# Pi_OS_v1.net
KiCad netlist of a schematic drawn in EAGLE
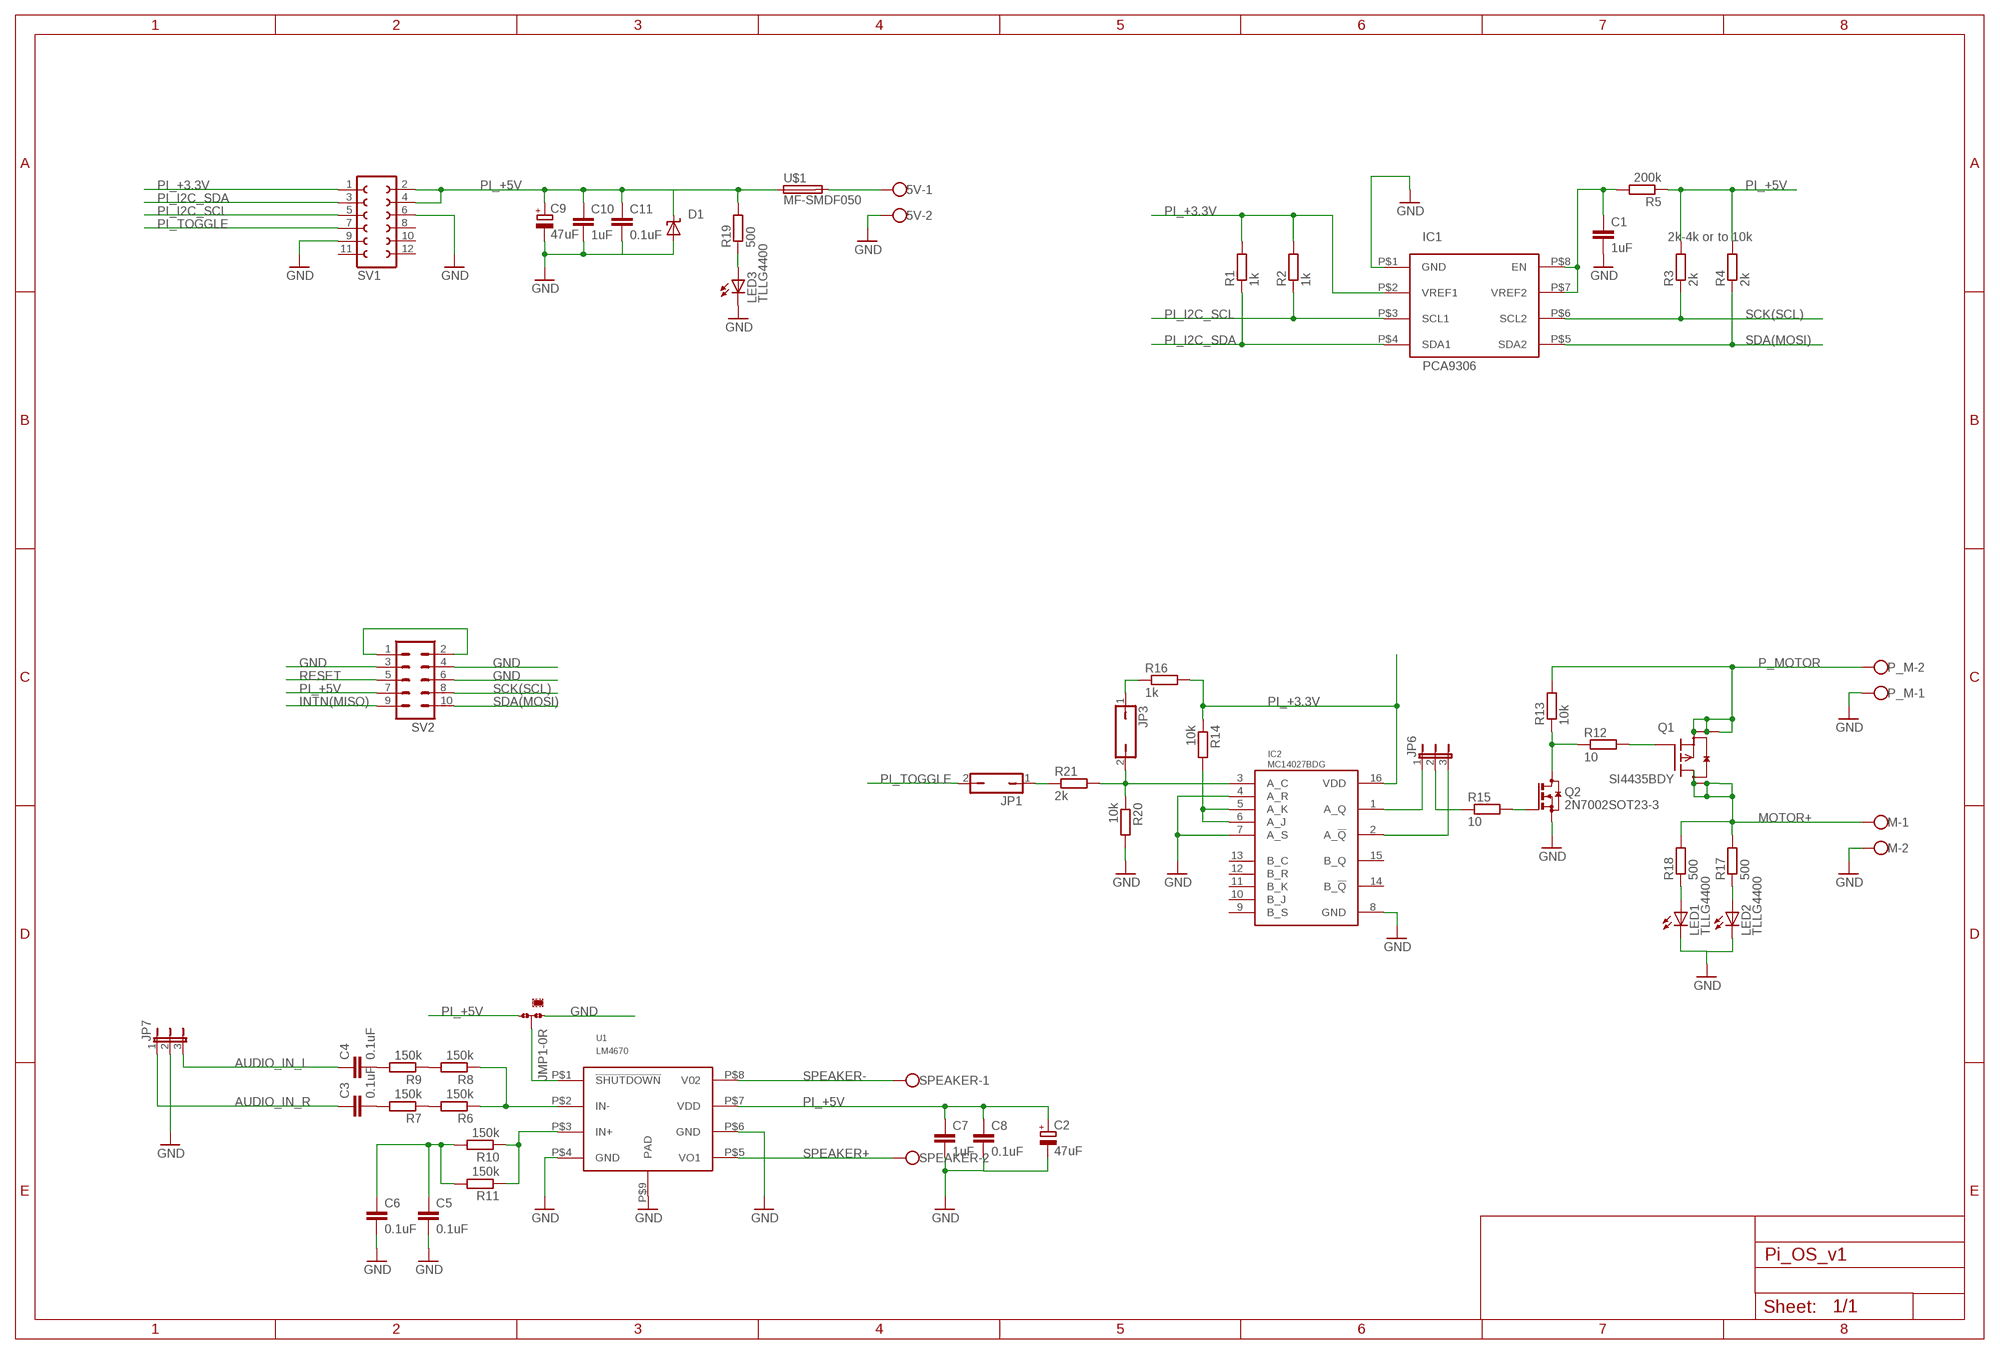
[diagram p0: schematic, sheet 1]

(export (version "E")
  (design (tool "Eeschema 10.0.6"))
  (components
    (comp (ref "5V")
      (value "W237-102")
      (footprint "eagle-import:W237-102")
      (fields (field (name "MPN") "237-102"))
      (libsource (lib "eagle-import") (part "W237-102"))
    )
    (comp (ref "C1")
      (value "1uF")
      (footprint "eagle-import:C1206")
      (libsource (lib "eagle-import") (part "C-EUC1206"))
    )
    (comp (ref "C2")
      (value "47uF")
      (footprint "eagle-import:153CLV-0505")
      (libsource (lib "eagle-import") (part "CPOL-EU153CLV-0505"))
    )
    (comp (ref "C3")
      (value "0.1uF")
      (footprint "eagle-import:C1206")
      (libsource (lib "eagle-import") (part "C-EUC1206"))
    )
    (comp (ref "C4")
      (value "0.1uF")
      (footprint "eagle-import:C1206")
      (libsource (lib "eagle-import") (part "C-EUC1206"))
    )
    (comp (ref "C5")
      (value "0.1uF")
      (footprint "eagle-import:C1206")
      (libsource (lib "eagle-import") (part "C-EUC1206"))
    )
    (comp (ref "C6")
      (value "0.1uF")
      (footprint "eagle-import:C1206")
      (libsource (lib "eagle-import") (part "C-EUC1206"))
    )
    (comp (ref "C7")
      (value "1uF")
      (footprint "eagle-import:C1206")
      (libsource (lib "eagle-import") (part "C-EUC1206"))
    )
    (comp (ref "C8")
      (value "0.1uF")
      (footprint "eagle-import:C1206")
      (libsource (lib "eagle-import") (part "C-EUC1206"))
    )
    (comp (ref "C9")
      (value "47uF")
      (footprint "eagle-import:153CLV-0505")
      (libsource (lib "eagle-import") (part "CPOL-EU153CLV-0505"))
    )
    (comp (ref "C10")
      (value "1uF")
      (footprint "eagle-import:C1206")
      (libsource (lib "eagle-import") (part "C-EUC1206"))
    )
    (comp (ref "C11")
      (value "0.1uF")
      (footprint "eagle-import:C1206")
      (libsource (lib "eagle-import") (part "C-EUC1206"))
    )
    (comp (ref "D1")
      (value "SUPPRESSOR-SMBJ")
      (footprint "eagle-import:SMBJ")
      (libsource (lib "eagle-import") (part "SUPPRESSOR-SMBJ"))
    )
    (comp (ref "IC1")
      (value "PCA9306")
      (footprint "eagle-import:TSSOP8")
      (libsource (lib "eagle-import") (part "PCA9306"))
    )
    (comp (ref "IC2")
      (value "MC14027BDG")
      (footprint "eagle-import:SOIC16")
      (libsource (lib "eagle-import") (part "MC14027BDG"))
    )
    (comp (ref "JMP1")
      (value "0R-JUMPB")
      (footprint "eagle-import:B0R-JMP")
      (libsource (lib "eagle-import") (part "0R-JUMPB"))
    )
    (comp (ref "JP1")
      (value "JP1Q")
      (footprint "eagle-import:JP1")
      (libsource (lib "eagle-import") (part "JP1Q"))
    )
    (comp (ref "JP3")
      (value "JP1Q")
      (footprint "eagle-import:JP1")
      (libsource (lib "eagle-import") (part "JP1Q"))
    )
    (comp (ref "JP6")
      (value "JP2E")
      (footprint "eagle-import:JP2")
      (libsource (lib "eagle-import") (part "JP2E"))
    )
    (comp (ref "JP7")
      (value "JP2E")
      (footprint "eagle-import:JP2")
      (libsource (lib "eagle-import") (part "JP2E"))
    )
    (comp (ref "LED1")
      (value "TLLG4400")
      (footprint "eagle-import:LED3MM")
      (fields (field (name "MF") "VISHAY SEMICONDUCTOR"))
      (libsource (lib "eagle-import") (part "TLLG4400"))
    )
    (comp (ref "LED2")
      (value "TLLG4400")
      (footprint "eagle-import:LED3MM")
      (fields (field (name "MF") "VISHAY SEMICONDUCTOR"))
      (libsource (lib "eagle-import") (part "TLLG4400"))
    )
    (comp (ref "LED3")
      (value "TLLG4400")
      (footprint "eagle-import:LED3MM")
      (fields (field (name "MF") "VISHAY SEMICONDUCTOR"))
      (libsource (lib "eagle-import") (part "TLLG4400"))
    )
    (comp (ref "M")
      (value "W237-102")
      (footprint "eagle-import:W237-102")
      (fields (field (name "MPN") "237-102"))
      (libsource (lib "eagle-import") (part "W237-102"))
    )
    (comp (ref "P_M")
      (value "W237-102")
      (footprint "eagle-import:W237-102")
      (fields (field (name "MPN") "237-102"))
      (libsource (lib "eagle-import") (part "W237-102"))
    )
    (comp (ref "Q1")
      (value "SI4435BDY")
      (footprint "eagle-import:SOIC8")
      (libsource (lib "eagle-import") (part "SI4435BDY"))
    )
    (comp (ref "Q2")
      (value "2N7002SOT23-3")
      (footprint "eagle-import:SOT23")
      (libsource (lib "eagle-import") (part "2N7002SOT23-3"))
    )
    (comp (ref "R1")
      (value "1k")
      (footprint "eagle-import:R0603")
      (libsource (lib "eagle-import") (part "R-EU_R0603"))
    )
    (comp (ref "R2")
      (value "1k")
      (footprint "eagle-import:R0603")
      (libsource (lib "eagle-import") (part "R-EU_R0603"))
    )
    (comp (ref "R3")
      (value "2k")
      (footprint "eagle-import:R0603")
      (libsource (lib "eagle-import") (part "R-EU_R0603"))
    )
    (comp (ref "R4")
      (value "2k")
      (footprint "eagle-import:R0603")
      (libsource (lib "eagle-import") (part "R-EU_R0603"))
    )
    (comp (ref "R5")
      (value "200k")
      (footprint "eagle-import:R0603")
      (libsource (lib "eagle-import") (part "R-EU_R0603"))
    )
    (comp (ref "R6")
      (value "150k")
      (footprint "eagle-import:R0603")
      (libsource (lib "eagle-import") (part "R-EU_R0603"))
    )
    (comp (ref "R7")
      (value "150k")
      (footprint "eagle-import:R0603")
      (libsource (lib "eagle-import") (part "R-EU_R0603"))
    )
    (comp (ref "R8")
      (value "150k")
      (footprint "eagle-import:R0603")
      (libsource (lib "eagle-import") (part "R-EU_R0603"))
    )
    (comp (ref "R9")
      (value "150k")
      (footprint "eagle-import:R0603")
      (libsource (lib "eagle-import") (part "R-EU_R0603"))
    )
    (comp (ref "R10")
      (value "150k")
      (footprint "eagle-import:R0603")
      (libsource (lib "eagle-import") (part "R-EU_R0603"))
    )
    (comp (ref "R11")
      (value "150k")
      (footprint "eagle-import:R0603")
      (libsource (lib "eagle-import") (part "R-EU_R0603"))
    )
    (comp (ref "R12")
      (value "10")
      (footprint "eagle-import:R0603")
      (libsource (lib "eagle-import") (part "R-EU_R0603"))
    )
    (comp (ref "R13")
      (value "10k")
      (footprint "eagle-import:R0603")
      (libsource (lib "eagle-import") (part "R-EU_R0603"))
    )
    (comp (ref "R14")
      (value "10k")
      (footprint "eagle-import:R0603")
      (libsource (lib "eagle-import") (part "R-EU_R0603"))
    )
    (comp (ref "R15")
      (value "10")
      (footprint "eagle-import:R0603")
      (libsource (lib "eagle-import") (part "R-EU_R0603"))
    )
    (comp (ref "R16")
      (value "1k")
      (footprint "eagle-import:R0603")
      (libsource (lib "eagle-import") (part "R-EU_R0603"))
    )
    (comp (ref "R17")
      (value "500")
      (footprint "eagle-import:R0603")
      (libsource (lib "eagle-import") (part "R-EU_R0603"))
    )
    (comp (ref "R18")
      (value "500")
      (footprint "eagle-import:R0603")
      (libsource (lib "eagle-import") (part "R-EU_R0603"))
    )
    (comp (ref "R19")
      (value "500")
      (footprint "eagle-import:R0603")
      (libsource (lib "eagle-import") (part "R-EU_R0603"))
    )
    (comp (ref "R20")
      (value "10k")
      (footprint "eagle-import:R0603")
      (libsource (lib "eagle-import") (part "R-EU_R0603"))
    )
    (comp (ref "R21")
      (value "2k")
      (footprint "eagle-import:R0603")
      (libsource (lib "eagle-import") (part "R-EU_R0603"))
    )
    (comp (ref "SPEAKER")
      (value "W237-102")
      (footprint "eagle-import:W237-102")
      (fields (field (name "MPN") "237-102"))
      (libsource (lib "eagle-import") (part "W237-102"))
    )
    (comp (ref "SV1")
      (value "FE06-2")
      (footprint "eagle-import:FE06-2")
      (libsource (lib "eagle-import") (part "FE06-2"))
    )
    (comp (ref "SV2")
      (value "MA05-2")
      (footprint "eagle-import:MA05-2")
      (libsource (lib "eagle-import") (part "MA05-2"))
    )
    (comp (ref "U$1")
      (value "MF-SMDF050")
      (footprint "eagle-import:MF-SMDF050")
      (libsource (lib "eagle-import") (part "MF-SMDF050"))
    )
    (comp (ref "U1")
      (value "LM4670")
      (footprint "eagle-import:MSOP-08P")
      (libsource (lib "eagle-import") (part "LM4670"))
    )
  )
  (nets
    (net (code "1") (name "/AUDIO_IN_L") (class "Default")
      (node (ref "C4") (pin "1") (pinfunction "1_1") (pintype "passive"))
      (node (ref "JP7") (pin "3") (pinfunction "3_3") (pintype "passive"))
    )
    (net (code "2") (name "/AUDIO_IN_R") (class "Default")
      (node (ref "C3") (pin "1") (pinfunction "1_1") (pintype "passive"))
      (node (ref "JP7") (pin "1") (pinfunction "1_1") (pintype "passive"))
    )
    (net (code "3") (name "/INTN(MISO)") (class "Default")
      (node (ref "SV2") (pin "9") (pinfunction "9_9") (pintype "passive"))
    )
    (net (code "4") (name "/MOTOR+") (class "Default")
      (node (ref "M") (pin "1") (pinfunction "KL_1") (pintype "passive"))
      (node (ref "Q1") (pin "5") (pinfunction "D_5") (pintype "passive"))
      (node (ref "Q1") (pin "6") (pinfunction "D_6") (pintype "passive"))
      (node (ref "Q1") (pin "7") (pinfunction "D_7") (pintype "passive"))
      (node (ref "Q1") (pin "8") (pinfunction "D_8") (pintype "passive"))
      (node (ref "R17") (pin "2") (pinfunction "2_2") (pintype "passive"))
      (node (ref "R18") (pin "2") (pinfunction "2_2") (pintype "passive"))
    )
    (net (code "5") (name "/PI_+3.3V") (class "Default")
      (node (ref "IC1") (pin "P$2") (pinfunction "VREF1_P$2") (pintype "bidirectional"))
      (node (ref "IC2") (pin "16") (pinfunction "VDD_16") (pintype "bidirectional"))
      (node (ref "R1") (pin "2") (pinfunction "2_2") (pintype "passive"))
      (node (ref "R14") (pin "1") (pinfunction "1_1") (pintype "passive"))
      (node (ref "R16") (pin "2") (pinfunction "2_2") (pintype "passive"))
      (node (ref "R2") (pin "2") (pinfunction "2_2") (pintype "passive"))
      (node (ref "SV1") (pin "1") (pinfunction "1_1") (pintype "passive"))
    )
    (net (code "6") (name "/PI_+5V") (class "Default")
      (node (ref "C10") (pin "1") (pinfunction "1_1") (pintype "passive"))
      (node (ref "C11") (pin "1") (pinfunction "1_1") (pintype "passive"))
      (node (ref "C2") (pin "+") (pinfunction "+_+") (pintype "passive"))
      (node (ref "C7") (pin "1") (pinfunction "1_1") (pintype "passive"))
      (node (ref "C8") (pin "1") (pinfunction "1_1") (pintype "passive"))
      (node (ref "C9") (pin "+") (pinfunction "+_+") (pintype "passive"))
      (node (ref "D1") (pin "C") (pinfunction "C_C") (pintype "passive"))
      (node (ref "JMP1") (pin "3") (pinfunction "3_3") (pintype "passive"))
      (node (ref "R19") (pin "2") (pinfunction "2_2") (pintype "passive"))
      (node (ref "R3") (pin "2") (pinfunction "2_2") (pintype "passive"))
      (node (ref "R4") (pin "2") (pinfunction "2_2") (pintype "passive"))
      (node (ref "R5") (pin "1") (pinfunction "1_1") (pintype "passive"))
      (node (ref "SV1") (pin "2") (pinfunction "2_2") (pintype "passive"))
      (node (ref "SV1") (pin "4") (pinfunction "4_4") (pintype "passive"))
      (node (ref "SV2") (pin "7") (pinfunction "7_7") (pintype "passive"))
      (node (ref "U$1") (pin "1") (pinfunction "1_1") (pintype "passive"))
      (node (ref "U1") (pin "P$7") (pinfunction "VDD_P$7") (pintype "power_in"))
    )
    (net (code "7") (name "/PI_I2C_SCL") (class "Default")
      (node (ref "IC1") (pin "P$3") (pinfunction "SCL1_P$3") (pintype "bidirectional"))
      (node (ref "R2") (pin "1") (pinfunction "1_1") (pintype "passive"))
      (node (ref "SV1") (pin "5") (pinfunction "5_5") (pintype "passive"))
    )
    (net (code "8") (name "/PI_I2C_SDA") (class "Default")
      (node (ref "IC1") (pin "P$4") (pinfunction "SDA1_P$4") (pintype "bidirectional"))
      (node (ref "R1") (pin "1") (pinfunction "1_1") (pintype "passive"))
      (node (ref "SV1") (pin "3") (pinfunction "3_3") (pintype "passive"))
    )
    (net (code "9") (name "/PI_TOGGLE") (class "Default")
      (node (ref "JP1") (pin "2") (pinfunction "2_2") (pintype "passive"))
      (node (ref "SV1") (pin "7") (pinfunction "7_7") (pintype "passive"))
    )
    (net (code "10") (name "/P_MOTOR") (class "Default")
      (node (ref "P_M") (pin "2") (pinfunction "KL_2") (pintype "passive"))
      (node (ref "Q1") (pin "1") (pinfunction "S_1") (pintype "passive"))
      (node (ref "Q1") (pin "2") (pinfunction "S_2") (pintype "passive"))
      (node (ref "Q1") (pin "3") (pinfunction "S_3") (pintype "passive"))
      (node (ref "R13") (pin "2") (pinfunction "2_2") (pintype "passive"))
    )
    (net (code "11") (name "/RESET") (class "Default")
      (node (ref "SV2") (pin "5") (pinfunction "5_5") (pintype "passive"))
    )
    (net (code "12") (name "/SCK(SCL)") (class "Default")
      (node (ref "IC1") (pin "P$6") (pinfunction "SCL2_P$6") (pintype "bidirectional"))
      (node (ref "R3") (pin "1") (pinfunction "1_1") (pintype "passive"))
      (node (ref "SV2") (pin "8") (pinfunction "8_8") (pintype "passive"))
    )
    (net (code "13") (name "/SDA(MOSI)") (class "Default")
      (node (ref "IC1") (pin "P$5") (pinfunction "SDA2_P$5") (pintype "bidirectional"))
      (node (ref "R4") (pin "1") (pinfunction "1_1") (pintype "passive"))
      (node (ref "SV2") (pin "10") (pinfunction "10_10") (pintype "passive"))
    )
    (net (code "14") (name "/SPEAKER+") (class "Default")
      (node (ref "SPEAKER") (pin "2") (pinfunction "KL_2") (pintype "passive"))
      (node (ref "U1") (pin "P$5") (pinfunction "VO1_P$5") (pintype "output"))
    )
    (net (code "15") (name "/SPEAKER-") (class "Default")
      (node (ref "SPEAKER") (pin "1") (pinfunction "KL_1") (pintype "passive"))
      (node (ref "U1") (pin "P$8") (pinfunction "V02_P$8") (pintype "output"))
    )
    (net (code "16") (name "GND") (class "Default")
      (node (ref "5V") (pin "2") (pinfunction "KL_2") (pintype "passive"))
      (node (ref "C1") (pin "2") (pinfunction "2_2") (pintype "passive"))
      (node (ref "C10") (pin "2") (pinfunction "2_2") (pintype "passive"))
      (node (ref "C11") (pin "2") (pinfunction "2_2") (pintype "passive"))
      (node (ref "C2") (pin "-") (pinfunction "-_-") (pintype "passive"))
      (node (ref "C5") (pin "2") (pinfunction "2_2") (pintype "passive"))
      (node (ref "C6") (pin "2") (pinfunction "2_2") (pintype "passive"))
      (node (ref "C7") (pin "2") (pinfunction "2_2") (pintype "passive"))
      (node (ref "C8") (pin "2") (pinfunction "2_2") (pintype "passive"))
      (node (ref "C9") (pin "-") (pinfunction "-_-") (pintype "passive"))
      (node (ref "D1") (pin "A") (pinfunction "A_A") (pintype "passive"))
      (node (ref "IC1") (pin "P$1") (pinfunction "GND_P$1") (pintype "bidirectional"))
      (node (ref "IC2") (pin "4") (pinfunction "A_R_4") (pintype "bidirectional"))
      (node (ref "IC2") (pin "7") (pinfunction "A_S_7") (pintype "bidirectional"))
      (node (ref "IC2") (pin "8") (pinfunction "GND_8") (pintype "bidirectional"))
      (node (ref "JMP1") (pin "1") (pinfunction "1_1") (pintype "passive"))
      (node (ref "JP7") (pin "2") (pinfunction "2_2") (pintype "passive"))
      (node (ref "LED1") (pin "K") (pinfunction "C_K") (pintype "passive"))
      (node (ref "LED2") (pin "K") (pinfunction "C_K") (pintype "passive"))
      (node (ref "LED3") (pin "K") (pinfunction "C_K") (pintype "passive"))
      (node (ref "M") (pin "2") (pinfunction "KL_2") (pintype "passive"))
      (node (ref "P_M") (pin "1") (pinfunction "KL_1") (pintype "passive"))
      (node (ref "Q2") (pin "2") (pinfunction "S_2") (pintype "passive"))
      (node (ref "R20") (pin "2") (pinfunction "2_2") (pintype "passive"))
      (node (ref "SV1") (pin "6") (pinfunction "6_6") (pintype "passive"))
      (node (ref "SV1") (pin "9") (pinfunction "9_9") (pintype "passive"))
      (node (ref "SV2") (pin "3") (pinfunction "3_3") (pintype "passive"))
      (node (ref "SV2") (pin "4") (pinfunction "4_4") (pintype "passive"))
      (node (ref "SV2") (pin "6") (pinfunction "6_6") (pintype "passive"))
      (node (ref "U1") (pin "P$4") (pinfunction "GND_P$4") (pintype "power_in"))
      (node (ref "U1") (pin "P$6") (pinfunction "GND_P$6") (pintype "power_in"))
      (node (ref "U1") (pin "P$9") (pinfunction "PAD_P$9") (pintype "power_in"))
    )
    (net (code "17") (name "Net-(5VA-KL)") (class "Default")
      (node (ref "5V") (pin "1") (pinfunction "KL_1") (pintype "passive"))
      (node (ref "U$1") (pin "2") (pinfunction "2_2") (pintype "passive"))
    )
    (net (code "18") (name "Net-(C3-Pad2)") (class "Default")
      (node (ref "C3") (pin "2") (pinfunction "2_2") (pintype "passive"))
      (node (ref "R7") (pin "2") (pinfunction "2_2") (pintype "passive"))
    )
    (net (code "19") (name "Net-(C4-Pad2)") (class "Default")
      (node (ref "C4") (pin "2") (pinfunction "2_2") (pintype "passive"))
      (node (ref "R9") (pin "2") (pinfunction "2_2") (pintype "passive"))
    )
    (net (code "20") (name "Net-(C5-Pad1)") (class "Default")
      (node (ref "C5") (pin "1") (pinfunction "1_1") (pintype "passive"))
      (node (ref "C6") (pin "1") (pinfunction "1_1") (pintype "passive"))
      (node (ref "R10") (pin "2") (pinfunction "2_2") (pintype "passive"))
      (node (ref "R11") (pin "2") (pinfunction "2_2") (pintype "passive"))
    )
    (net (code "21") (name "Net-(IC1-EN)") (class "Default")
      (node (ref "C1") (pin "1") (pinfunction "1_1") (pintype "passive"))
      (node (ref "IC1") (pin "P$7") (pinfunction "VREF2_P$7") (pintype "bidirectional"))
      (node (ref "IC1") (pin "P$8") (pinfunction "EN_P$8") (pintype "bidirectional"))
      (node (ref "R5") (pin "2") (pinfunction "2_2") (pintype "passive"))
    )
    (net (code "22") (name "Net-(IC2-A_C)") (class "Default")
      (node (ref "IC2") (pin "3") (pinfunction "A_C_3") (pintype "bidirectional"))
      (node (ref "JP3") (pin "2") (pinfunction "2_2") (pintype "passive"))
      (node (ref "R20") (pin "1") (pinfunction "1_1") (pintype "passive"))
      (node (ref "R21") (pin "2") (pinfunction "2_2") (pintype "passive"))
    )
    (net (code "23") (name "Net-(IC2-A_J)") (class "Default")
      (node (ref "IC2") (pin "5") (pinfunction "A_K_5") (pintype "bidirectional"))
      (node (ref "IC2") (pin "6") (pinfunction "A_J_6") (pintype "bidirectional"))
      (node (ref "R14") (pin "2") (pinfunction "2_2") (pintype "passive"))
    )
    (net (code "24") (name "Net-(IC2-A_Q)") (class "Default")
      (node (ref "IC2") (pin "1") (pinfunction "A_Q_1") (pintype "bidirectional"))
      (node (ref "JP6") (pin "1") (pinfunction "1_1") (pintype "passive"))
    )
    (net (code "25") (name "Net-(IC2-A_~{Q})") (class "Default")
      (node (ref "IC2") (pin "2") (pinfunction "A_~{Q}_2") (pintype "bidirectional"))
      (node (ref "JP6") (pin "3") (pinfunction "3_3") (pintype "passive"))
    )
    (net (code "26") (name "Net-(JP1-Pad1)") (class "Default")
      (node (ref "JP1") (pin "1") (pinfunction "1_1") (pintype "passive"))
      (node (ref "R21") (pin "1") (pinfunction "1_1") (pintype "passive"))
    )
    (net (code "27") (name "Net-(JP3-Pad1)") (class "Default")
      (node (ref "JP3") (pin "1") (pinfunction "1_1") (pintype "passive"))
      (node (ref "R16") (pin "1") (pinfunction "1_1") (pintype "passive"))
    )
    (net (code "28") (name "Net-(JP6-Pad2)") (class "Default")
      (node (ref "JP6") (pin "2") (pinfunction "2_2") (pintype "passive"))
      (node (ref "R15") (pin "1") (pinfunction "1_1") (pintype "passive"))
    )
    (net (code "29") (name "Net-(LED1-PadA)") (class "Default")
      (node (ref "LED1") (pin "A") (pinfunction "A_A") (pintype "passive"))
      (node (ref "R18") (pin "1") (pinfunction "1_1") (pintype "passive"))
    )
    (net (code "30") (name "Net-(LED2-PadA)") (class "Default")
      (node (ref "LED2") (pin "A") (pinfunction "A_A") (pintype "passive"))
      (node (ref "R17") (pin "1") (pinfunction "1_1") (pintype "passive"))
    )
    (net (code "31") (name "Net-(LED3-PadA)") (class "Default")
      (node (ref "LED3") (pin "A") (pinfunction "A_A") (pintype "passive"))
      (node (ref "R19") (pin "1") (pinfunction "1_1") (pintype "passive"))
    )
    (net (code "32") (name "Net-(Q1-G)") (class "Default")
      (node (ref "Q1") (pin "4") (pinfunction "G_4") (pintype "passive"))
      (node (ref "R12") (pin "2") (pinfunction "2_2") (pintype "passive"))
    )
    (net (code "33") (name "Net-(Q2-D)") (class "Default")
      (node (ref "Q2") (pin "3") (pinfunction "D_3") (pintype "passive"))
      (node (ref "R12") (pin "1") (pinfunction "1_1") (pintype "passive"))
      (node (ref "R13") (pin "1") (pinfunction "1_1") (pintype "passive"))
    )
    (net (code "34") (name "Net-(Q2-G)") (class "Default")
      (node (ref "Q2") (pin "1") (pinfunction "G_1") (pintype "passive"))
      (node (ref "R15") (pin "2") (pinfunction "2_2") (pintype "passive"))
    )
    (net (code "35") (name "Net-(R6-Pad2)") (class "Default")
      (node (ref "R6") (pin "2") (pinfunction "2_2") (pintype "passive"))
      (node (ref "R7") (pin "1") (pinfunction "1_1") (pintype "passive"))
    )
    (net (code "36") (name "Net-(R8-Pad2)") (class "Default")
      (node (ref "R8") (pin "2") (pinfunction "2_2") (pintype "passive"))
      (node (ref "R9") (pin "1") (pinfunction "1_1") (pintype "passive"))
    )
    (net (code "37") (name "Net-(SV2-Pad1)") (class "Default")
      (node (ref "SV2") (pin "1") (pinfunction "1_1") (pintype "passive"))
      (node (ref "SV2") (pin "2") (pinfunction "2_2") (pintype "passive"))
    )
    (net (code "38") (name "Net-(U1-IN+)") (class "Default")
      (node (ref "R10") (pin "1") (pinfunction "1_1") (pintype "passive"))
      (node (ref "R11") (pin "1") (pinfunction "1_1") (pintype "passive"))
      (node (ref "U1") (pin "P$3") (pinfunction "IN+_P$3") (pintype "input"))
    )
    (net (code "39") (name "Net-(U1-IN-)") (class "Default")
      (node (ref "R6") (pin "1") (pinfunction "1_1") (pintype "passive"))
      (node (ref "R8") (pin "1") (pinfunction "1_1") (pintype "passive"))
      (node (ref "U1") (pin "P$2") (pinfunction "IN-_P$2") (pintype "input"))
    )
    (net (code "40") (name "Net-(U1-~{SHUTDOWN})") (class "Default")
      (node (ref "JMP1") (pin "2") (pinfunction "2_2") (pintype "passive"))
      (node (ref "U1") (pin "P$1") (pinfunction "~{SHUTDOWN}_P$1") (pintype "input"))
    )
    (net (code "41") (name "unconnected-(IC2-B_C-Pad13)") (class "Default")
      (node (ref "IC2") (pin "13") (pinfunction "B_C_13") (pintype "bidirectional"))
    )
    (net (code "42") (name "unconnected-(IC2-B_J-Pad10)") (class "Default")
      (node (ref "IC2") (pin "10") (pinfunction "B_J_10") (pintype "bidirectional"))
    )
    (net (code "43") (name "unconnected-(IC2-B_K-Pad11)") (class "Default")
      (node (ref "IC2") (pin "11") (pinfunction "B_K_11") (pintype "bidirectional"))
    )
    (net (code "44") (name "unconnected-(IC2-B_Q-Pad15)") (class "Default")
      (node (ref "IC2") (pin "15") (pinfunction "B_Q_15") (pintype "bidirectional"))
    )
    (net (code "45") (name "unconnected-(IC2-B_R-Pad12)") (class "Default")
      (node (ref "IC2") (pin "12") (pinfunction "B_R_12") (pintype "bidirectional"))
    )
    (net (code "46") (name "unconnected-(IC2-B_S-Pad9)") (class "Default")
      (node (ref "IC2") (pin "9") (pinfunction "B_S_9") (pintype "bidirectional"))
    )
    (net (code "47") (name "unconnected-(IC2-B_~{Q}-Pad14)") (class "Default")
      (node (ref "IC2") (pin "14") (pinfunction "B_~{Q}_14") (pintype "bidirectional"))
    )
    (net (code "48") (name "unconnected-(SV1-Pad8)") (class "Default")
      (node (ref "SV1") (pin "8") (pinfunction "8_8") (pintype "passive"))
    )
    (net (code "49") (name "unconnected-(SV1-Pad10)") (class "Default")
      (node (ref "SV1") (pin "10") (pinfunction "10_10") (pintype "passive"))
    )
    (net (code "50") (name "unconnected-(SV1-Pad11)") (class "Default")
      (node (ref "SV1") (pin "11") (pinfunction "11_11") (pintype "passive"))
    )
    (net (code "51") (name "unconnected-(SV1-Pad12)") (class "Default")
      (node (ref "SV1") (pin "12") (pinfunction "12_12") (pintype "passive"))
    )
  )
)
